# schematic.net
KiCad netlist of a schematic drawn in EasyEDA
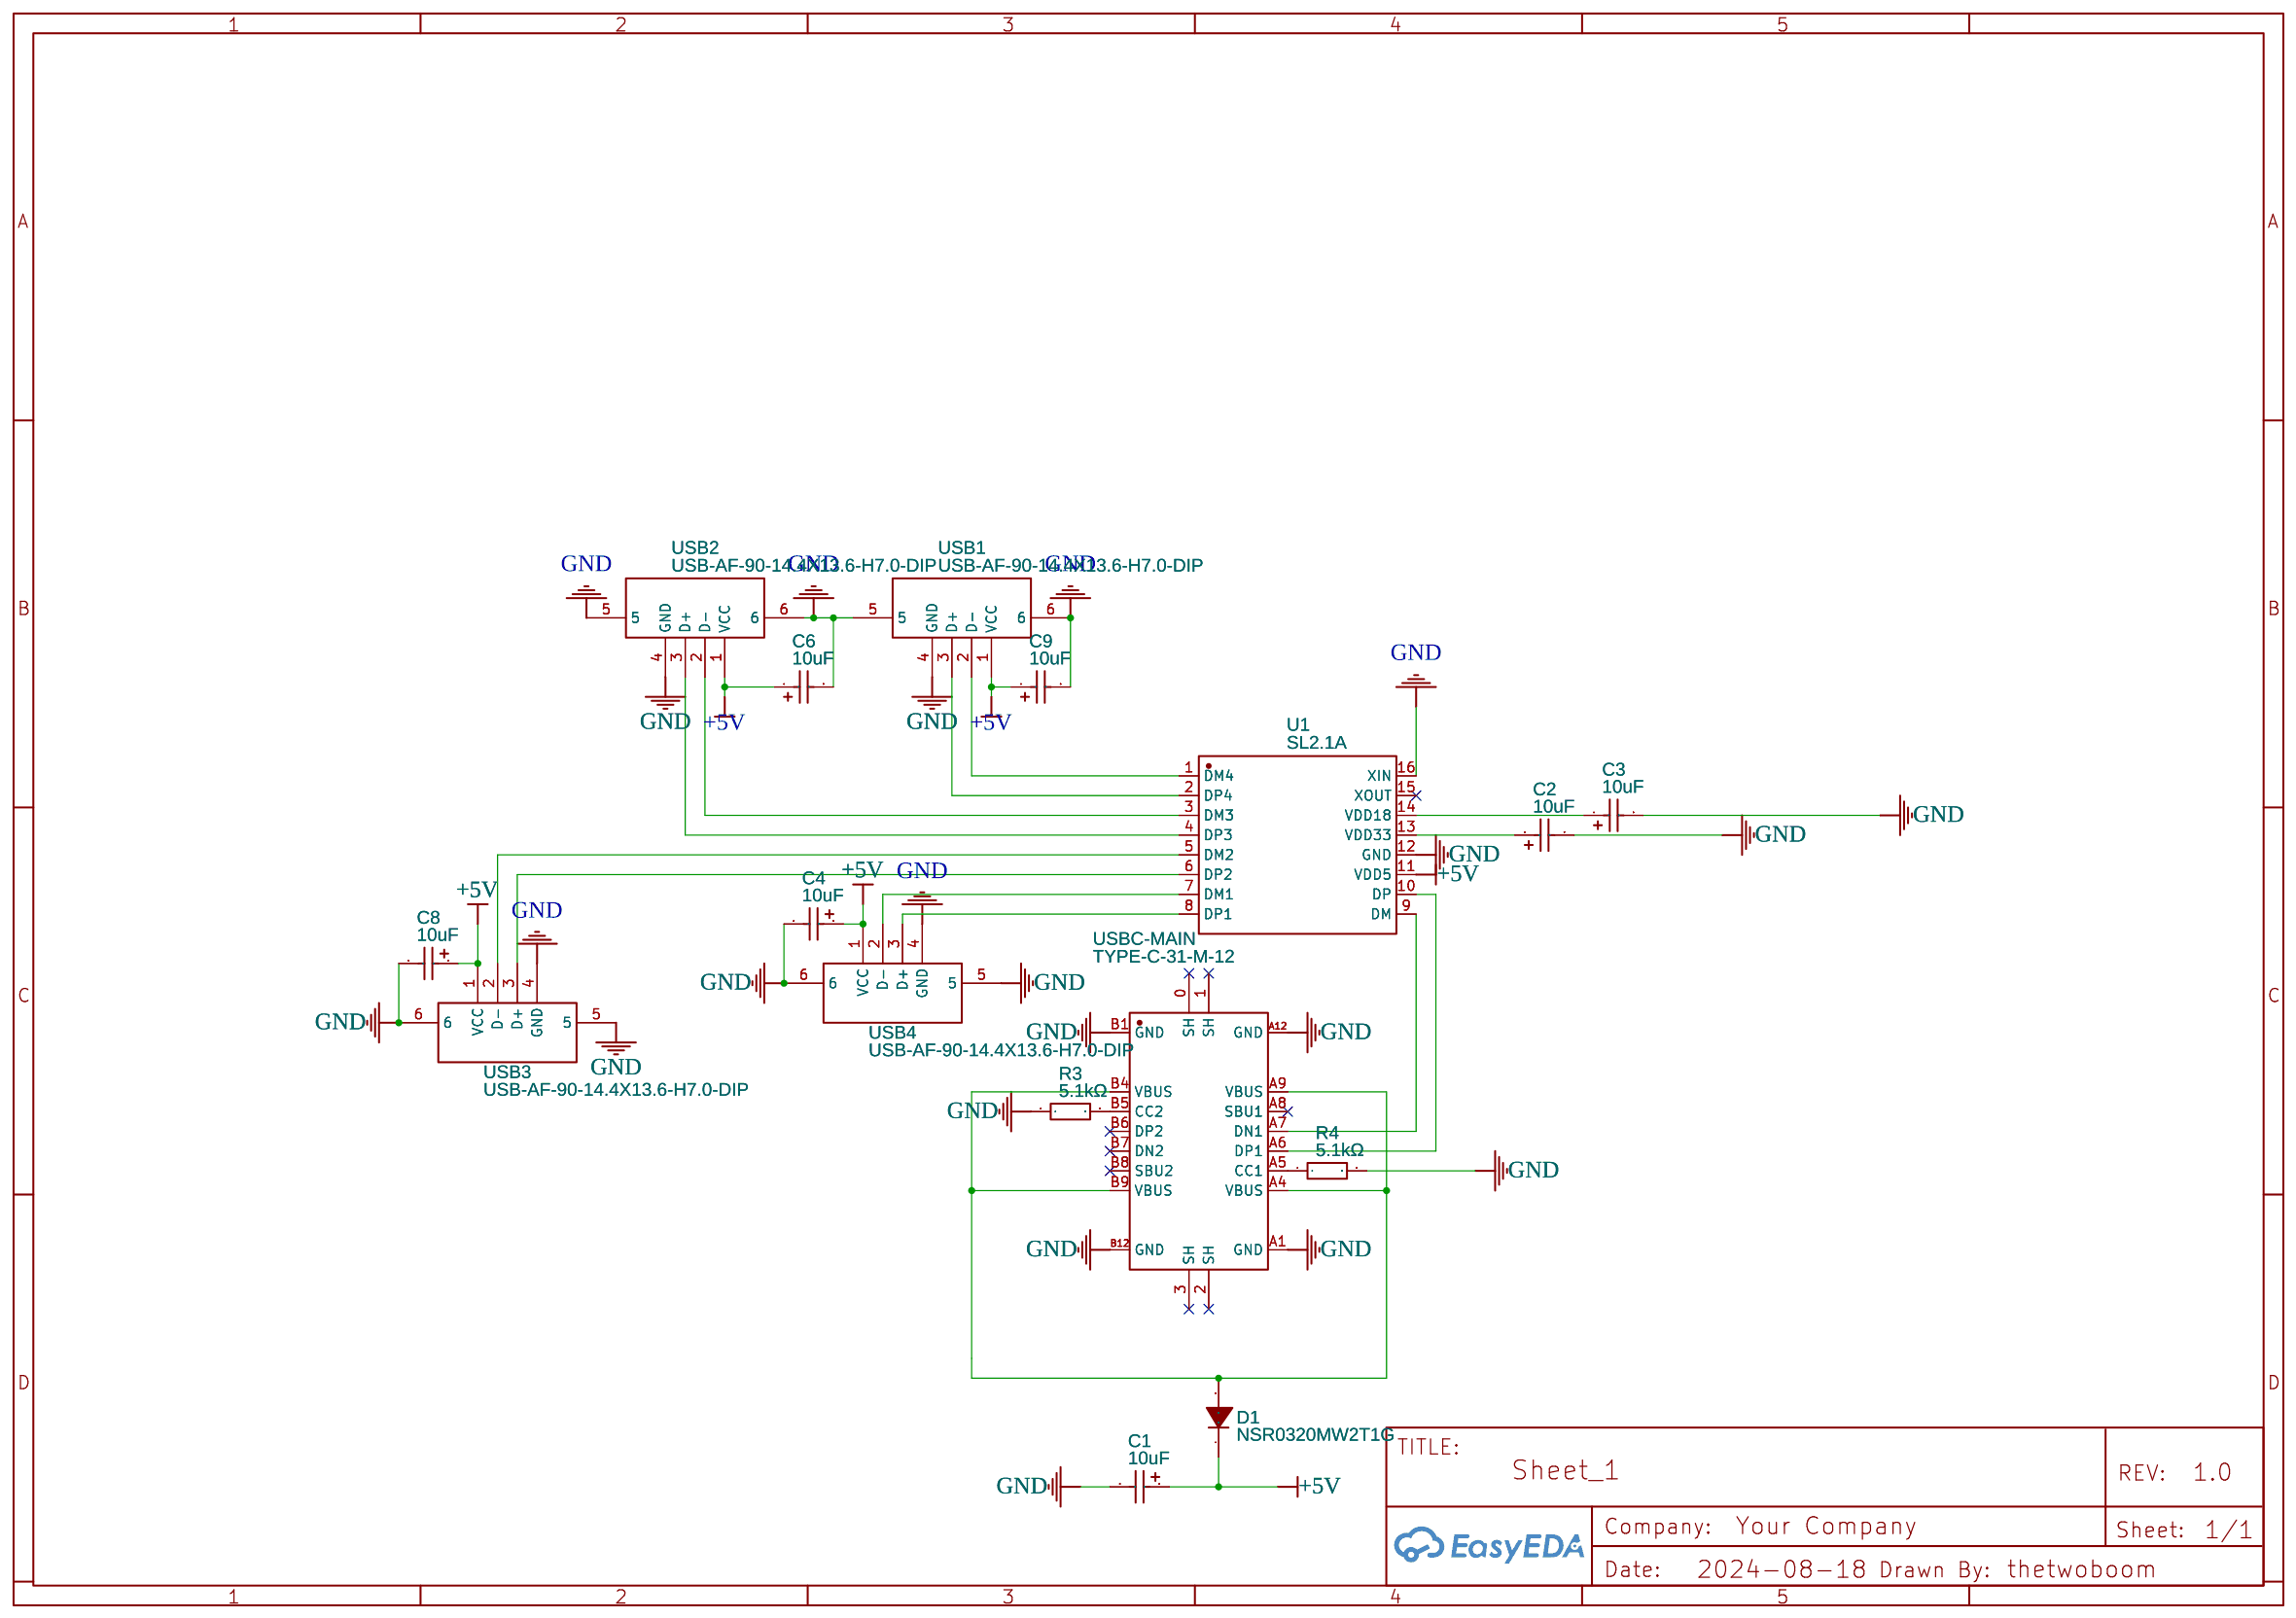
[diagram p0: schematic sheet]

(export (version "E")
  (design (tool "Eeschema 10.0.6"))
  (components
    (comp (ref "C1")
      (value "10uF")
      (fields (field (name "Manufacturer Part") "TAJA106K016RNJ") (field (name "Manufacturer") "Kyocera AVX"))
      (libsource (lib "") (part "TAJA106K016RNJ_1"))
    )
    (comp (ref "C2")
      (value "10uF")
      (fields (field (name "Manufacturer Part") "TAJA106K016RNJ") (field (name "Manufacturer") "Kyocera AVX"))
      (libsource (lib "") (part "TAJA106K016RNJ"))
    )
    (comp (ref "C3")
      (value "10uF")
      (fields (field (name "Manufacturer Part") "TAJA106K016RNJ") (field (name "Manufacturer") "Kyocera AVX"))
      (libsource (lib "") (part "TAJA106K016RNJ"))
    )
    (comp (ref "C4")
      (value "10uF")
      (fields (field (name "Manufacturer Part") "TAJA106K016RNJ") (field (name "Manufacturer") "Kyocera AVX"))
      (libsource (lib "") (part "TAJA106K016RNJ_1"))
    )
    (comp (ref "C6")
      (value "10uF")
      (fields (field (name "Manufacturer Part") "TAJA106K016RNJ") (field (name "Manufacturer") "Kyocera AVX"))
      (libsource (lib "") (part "TAJA106K016RNJ"))
    )
    (comp (ref "C8")
      (value "10uF")
      (fields (field (name "Manufacturer Part") "TAJA106K016RNJ") (field (name "Manufacturer") "Kyocera AVX"))
      (libsource (lib "") (part "TAJA106K016RNJ_1"))
    )
    (comp (ref "C9")
      (value "10uF")
      (fields (field (name "Manufacturer Part") "TAJA106K016RNJ") (field (name "Manufacturer") "Kyocera AVX"))
      (libsource (lib "") (part "TAJA106K016RNJ"))
    )
    (comp (ref "D1")
      (value "NSR0320MW2T1G")
      (fields (field (name "Manufacturer") "onsemi(安森美)"))
      (libsource (lib "") (part "NSR0320MW2T1G"))
    )
    (comp (ref "R3")
      (value "5.1kΩ")
      (fields
        (field (name "Manufacturer Part") "0805W8F5101T5E")
        (field (name "Manufacturer") "UNI-ROYAL(厚声)")
      )
      (libsource (lib "") (part "0805W8F5101T5E"))
    )
    (comp (ref "R4")
      (value "5.1kΩ")
      (fields
        (field (name "Manufacturer Part") "0805W8F5101T5E")
        (field (name "Manufacturer") "UNI-ROYAL(厚声)")
      )
      (libsource (lib "") (part "0805W8F5101T5E"))
    )
    (comp (ref "U1")
      (value "SL2.1A")
      (fields (field (name "Manufacturer") "CoreChips(和芯润德)"))
      (libsource (lib "") (part "SL2.1A"))
    )
    (comp (ref "USB1")
      (value "USB-AF-90-14.4X13.6-H7.0-DIP")
      (fields (field (name "Manufacturer Part") "903-131A1011D10100") (field (name "Manufacturer") "精拓金"))
      (libsource (lib "") (part "USB-AF-90-14.4X13.6-H7.0-DIP_1"))
    )
    (comp (ref "USB2")
      (value "USB-AF-90-14.4X13.6-H7.0-DIP")
      (fields (field (name "Manufacturer Part") "903-131A1011D10100") (field (name "Manufacturer") "精拓金"))
      (libsource (lib "") (part "USB-AF-90-14.4X13.6-H7.0-DIP_1"))
    )
    (comp (ref "USB3")
      (value "USB-AF-90-14.4X13.6-H7.0-DIP")
      (fields (field (name "Manufacturer Part") "903-131A1011D10100") (field (name "Manufacturer") "精拓金"))
      (libsource (lib "") (part "USB-AF-90-14.4X13.6-H7.0-DIP"))
    )
    (comp (ref "USB4")
      (value "USB-AF-90-14.4X13.6-H7.0-DIP")
      (fields (field (name "Manufacturer Part") "903-131A1011D10100") (field (name "Manufacturer") "精拓金"))
      (libsource (lib "") (part "USB-AF-90-14.4X13.6-H7.0-DIP"))
    )
    (comp (ref "USBC-MAIN")
      (value "TYPE-C-31-M-12")
      (fields (field (name "Manufacturer") "韩国韩荣"))
      (libsource (lib "") (part "TYPE-C-31-M-12"))
    )
  )
  (nets
    (net (code "1") (name "+5V") (class "Default")
      (node (ref "C1") (pin "1") (pinfunction "1_1") (pintype "input"))
      (node (ref "C4") (pin "1") (pinfunction "1_1") (pintype "input"))
      (node (ref "C6") (pin "1") (pinfunction "1_1") (pintype "input"))
      (node (ref "C8") (pin "1") (pinfunction "1_1") (pintype "input"))
      (node (ref "C9") (pin "1") (pinfunction "1_1") (pintype "input"))
      (node (ref "D1") (pin "1") (pinfunction "C_1") (pintype "unspecified"))
      (node (ref "U1") (pin "11") (pinfunction "VDD5_11") (pintype "unspecified"))
      (node (ref "USB1") (pin "1") (pinfunction "VCC_1") (pintype "unspecified"))
      (node (ref "USB2") (pin "1") (pinfunction "VCC_1") (pintype "unspecified"))
      (node (ref "USB3") (pin "1") (pinfunction "VCC_1") (pintype "unspecified"))
      (node (ref "USB4") (pin "1") (pinfunction "VCC_1") (pintype "unspecified"))
    )
    (net (code "2") (name "GND") (class "Default")
      (node (ref "C1") (pin "2") (pinfunction "2_2") (pintype "input"))
      (node (ref "C2") (pin "2") (pinfunction "2_2") (pintype "input"))
      (node (ref "C3") (pin "2") (pinfunction "2_2") (pintype "input"))
      (node (ref "C4") (pin "2") (pinfunction "2_2") (pintype "input"))
      (node (ref "C6") (pin "2") (pinfunction "2_2") (pintype "input"))
      (node (ref "C8") (pin "2") (pinfunction "2_2") (pintype "input"))
      (node (ref "C9") (pin "2") (pinfunction "2_2") (pintype "input"))
      (node (ref "R3") (pin "1") (pinfunction "1_1") (pintype "input"))
      (node (ref "R4") (pin "2") (pinfunction "2_2") (pintype "input"))
      (node (ref "U1") (pin "12") (pinfunction "GND_12") (pintype "unspecified"))
      (node (ref "U1") (pin "16") (pinfunction "XIN_16") (pintype "unspecified"))
      (node (ref "USB1") (pin "4") (pinfunction "GND_4") (pintype "unspecified"))
      (node (ref "USB1") (pin "5") (pinfunction "5_5") (pintype "unspecified"))
      (node (ref "USB1") (pin "6") (pinfunction "6_6") (pintype "unspecified"))
      (node (ref "USB2") (pin "4") (pinfunction "GND_4") (pintype "unspecified"))
      (node (ref "USB2") (pin "5") (pinfunction "5_5") (pintype "unspecified"))
      (node (ref "USB2") (pin "6") (pinfunction "6_6") (pintype "unspecified"))
      (node (ref "USB3") (pin "4") (pinfunction "GND_4") (pintype "unspecified"))
      (node (ref "USB3") (pin "5") (pinfunction "5_5") (pintype "unspecified"))
      (node (ref "USB3") (pin "6") (pinfunction "6_6") (pintype "unspecified"))
      (node (ref "USB4") (pin "4") (pinfunction "GND_4") (pintype "unspecified"))
      (node (ref "USB4") (pin "5") (pinfunction "5_5") (pintype "unspecified"))
      (node (ref "USB4") (pin "6") (pinfunction "6_6") (pintype "unspecified"))
      (node (ref "USBC-MAIN") (pin "A1") (pinfunction "GND_A1") (pintype "unspecified"))
      (node (ref "USBC-MAIN") (pin "A12") (pinfunction "GND_A12") (pintype "unspecified"))
      (node (ref "USBC-MAIN") (pin "B1") (pinfunction "GND_B1") (pintype "unspecified"))
      (node (ref "USBC-MAIN") (pin "B12") (pinfunction "GND_B12") (pintype "unspecified"))
    )
    (net (code "3") (name "Net-(D1-A)") (class "Default")
      (node (ref "D1") (pin "2") (pinfunction "A_2") (pintype "unspecified"))
      (node (ref "USBC-MAIN") (pin "A4") (pinfunction "VBUS_A4") (pintype "unspecified"))
      (node (ref "USBC-MAIN") (pin "A9") (pinfunction "VBUS_A9") (pintype "unspecified"))
      (node (ref "USBC-MAIN") (pin "B4") (pinfunction "VBUS_B4") (pintype "unspecified"))
      (node (ref "USBC-MAIN") (pin "B9") (pinfunction "VBUS_B9") (pintype "unspecified"))
    )
    (net (code "4") (name "Net-(U1-DM)") (class "Default")
      (node (ref "U1") (pin "9") (pinfunction "DM_9") (pintype "unspecified"))
      (node (ref "USBC-MAIN") (pin "A7") (pinfunction "DN1_A7") (pintype "unspecified"))
    )
    (net (code "5") (name "Net-(U1-DM1)") (class "Default")
      (node (ref "U1") (pin "7") (pinfunction "DM1_7") (pintype "unspecified"))
      (node (ref "USB4") (pin "2") (pinfunction "D-_2") (pintype "unspecified"))
    )
    (net (code "6") (name "Net-(U1-DM2)") (class "Default")
      (node (ref "U1") (pin "5") (pinfunction "DM2_5") (pintype "unspecified"))
      (node (ref "USB3") (pin "2") (pinfunction "D-_2") (pintype "unspecified"))
    )
    (net (code "7") (name "Net-(U1-DM3)") (class "Default")
      (node (ref "U1") (pin "3") (pinfunction "DM3_3") (pintype "unspecified"))
      (node (ref "USB2") (pin "2") (pinfunction "D-_2") (pintype "unspecified"))
    )
    (net (code "8") (name "Net-(U1-DM4)") (class "Default")
      (node (ref "U1") (pin "1") (pinfunction "DM4_1") (pintype "unspecified"))
      (node (ref "USB1") (pin "2") (pinfunction "D-_2") (pintype "unspecified"))
    )
    (net (code "9") (name "Net-(U1-DP)") (class "Default")
      (node (ref "U1") (pin "10") (pinfunction "DP_10") (pintype "unspecified"))
      (node (ref "USBC-MAIN") (pin "A6") (pinfunction "DP1_A6") (pintype "unspecified"))
    )
    (net (code "10") (name "Net-(U1-DP1)") (class "Default")
      (node (ref "U1") (pin "8") (pinfunction "DP1_8") (pintype "unspecified"))
      (node (ref "USB4") (pin "3") (pinfunction "D+_3") (pintype "unspecified"))
    )
    (net (code "11") (name "Net-(U1-DP2)") (class "Default")
      (node (ref "U1") (pin "6") (pinfunction "DP2_6") (pintype "unspecified"))
      (node (ref "USB3") (pin "3") (pinfunction "D+_3") (pintype "unspecified"))
    )
    (net (code "12") (name "Net-(U1-DP3)") (class "Default")
      (node (ref "U1") (pin "4") (pinfunction "DP3_4") (pintype "unspecified"))
      (node (ref "USB2") (pin "3") (pinfunction "D+_3") (pintype "unspecified"))
    )
    (net (code "13") (name "Net-(U1-DP4)") (class "Default")
      (node (ref "U1") (pin "2") (pinfunction "DP4_2") (pintype "unspecified"))
      (node (ref "USB1") (pin "3") (pinfunction "D+_3") (pintype "unspecified"))
    )
    (net (code "14") (name "Net-(U1-VDD18)") (class "Default")
      (node (ref "C3") (pin "1") (pinfunction "1_1") (pintype "input"))
      (node (ref "U1") (pin "14") (pinfunction "VDD18_14") (pintype "unspecified"))
    )
    (net (code "15") (name "Net-(U1-VDD33)") (class "Default")
      (node (ref "C2") (pin "1") (pinfunction "1_1") (pintype "input"))
      (node (ref "U1") (pin "13") (pinfunction "VDD33_13") (pintype "unspecified"))
    )
    (net (code "16") (name "Net-(USBC-MAIN-CC1)") (class "Default")
      (node (ref "R4") (pin "1") (pinfunction "1_1") (pintype "input"))
      (node (ref "USBC-MAIN") (pin "A5") (pinfunction "CC1_A5") (pintype "unspecified"))
    )
    (net (code "17") (name "Net-(USBC-MAIN-CC2)") (class "Default")
      (node (ref "R3") (pin "2") (pinfunction "2_2") (pintype "input"))
      (node (ref "USBC-MAIN") (pin "B5") (pinfunction "CC2_B5") (pintype "unspecified"))
    )
    (net (code "18") (name "unconnected-(U1-XOUT-Pad15)") (class "Default")
      (node (ref "U1") (pin "15") (pinfunction "XOUT_15") (pintype "unspecified+no_connect"))
    )
    (net (code "19") (name "unconnected-(USBC-MAIN-DN2-PadB7)") (class "Default")
      (node (ref "USBC-MAIN") (pin "B7") (pinfunction "DN2_B7") (pintype "unspecified+no_connect"))
    )
    (net (code "20") (name "unconnected-(USBC-MAIN-DP2-PadB6)") (class "Default")
      (node (ref "USBC-MAIN") (pin "B6") (pinfunction "DP2_B6") (pintype "unspecified+no_connect"))
    )
    (net (code "21") (name "unconnected-(USBC-MAIN-SBU1-PadA8)") (class "Default")
      (node (ref "USBC-MAIN") (pin "A8") (pinfunction "SBU1_A8") (pintype "unspecified+no_connect"))
    )
    (net (code "22") (name "unconnected-(USBC-MAIN-SBU2-PadB8)") (class "Default")
      (node (ref "USBC-MAIN") (pin "B8") (pinfunction "SBU2_B8") (pintype "unspecified+no_connect"))
    )
    (net (code "23") (name "unconnected-(USBC-MAIN-SH-Pad0)") (class "Default")
      (node (ref "USBC-MAIN") (pin "0") (pinfunction "SH_0") (pintype "unspecified+no_connect"))
    )
    (net (code "24") (name "unconnected-(USBC-MAIN-SH-Pad1)") (class "Default")
      (node (ref "USBC-MAIN") (pin "1") (pinfunction "SH_1") (pintype "unspecified+no_connect"))
    )
    (net (code "25") (name "unconnected-(USBC-MAIN-SH-Pad2)") (class "Default")
      (node (ref "USBC-MAIN") (pin "2") (pinfunction "SH_2") (pintype "unspecified+no_connect"))
    )
    (net (code "26") (name "unconnected-(USBC-MAIN-SH-Pad3)") (class "Default")
      (node (ref "USBC-MAIN") (pin "3") (pinfunction "SH_3") (pintype "unspecified+no_connect"))
    )
  )
)
